# TF.net
KiCad netlist of a schematic drawn in Altium Designer
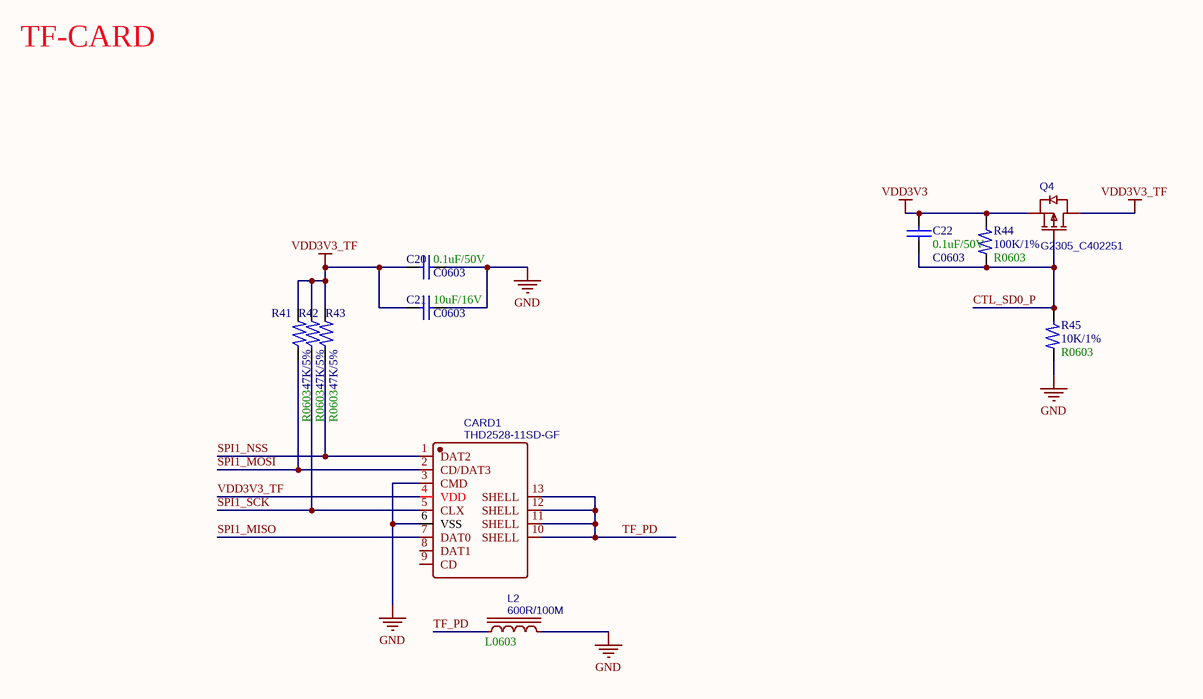
[diagram p0: TF.SchDoc]

(export (version "E")
  (design (tool "Eeschema 10.0.6"))
  (components
    (comp (ref "C20")
      (value "0.1uF/50V")
      (footprint "0603_C")
      (description "Capacitor")
      (fields (field (name "ALTIUM_VALUE") "C0603"))
      (libsource (lib "*") (part "CAP"))
    )
    (comp (ref "C21")
      (value "10uF/16V")
      (footprint "0603_C")
      (description "Capacitor")
      (fields (field (name "ALTIUM_VALUE") "C0603"))
      (libsource (lib "*") (part "CAP"))
    )
    (comp (ref "C22")
      (value "0.1uF/50V")
      (footprint "0603_C")
      (description "Capacitor")
      (fields (field (name "ALTIUM_VALUE") "C0603"))
      (libsource (lib "*") (part "CAP"))
    )
    (comp (ref "CARD1")
      (value "THD2528-11SD-GF")
      (footprint "TF-SMD_THD2528-11SD-GF")
      (fields (field (name "BOM_SUPPLIER PART") "C283232") (field (name "CONTRIBUTOR") "LCSC"))
      (libsource (lib "altium-import") (part "root_0_THD2528-11SD-GF_"))
    )
    (comp (ref "L2")
      (value "600R/100M")
      (footprint "0603_L")
      (fields
        (field (name "BOM_SUPPLIER PART") "C494701")
        (field (name "BOM_MANUFACTURER PART") "SCBM160808U600T")
        (field (name "ALTIUM_UNNAMED_1") "L0603")
        (field (name "CONTRIBUTOR") "LCSC")
      )
      (libsource (lib "altium-import") (part "root_0_SCBM160808U600T_"))
    )
    (comp (ref "Q4")
      (value "G2305_C402251")
      (footprint "SOT-23-3L")
      (fields
        (field (name "BOM_SUPPLIER PART") "C402251")
        (field (name "BOM_MANUFACTURER PART") "G2305")
        (field (name "CONTRIBUTOR") "LCSC")
      )
      (libsource (lib "altium-import") (part "root_1_mirrored_G2305_C402251_"))
    )
    (comp (ref "R41") (value "47K/5%") (footprint "R0603") (libsource (lib "*") (part "电阻")))
    (comp (ref "R42") (value "47K/5%") (footprint "R0603") (libsource (lib "*") (part "电阻")))
    (comp (ref "R43") (value "47K/5%") (footprint "R0603") (libsource (lib "*") (part "电阻")))
    (comp (ref "R44") (value "100K/1%") (footprint "R0603") (libsource (lib "*") (part "电阻")))
    (comp (ref "R45") (value "10K/1%") (footprint "R0603") (libsource (lib "*") (part "电阻")))
  )
  (nets
    (net (code "1") (name "/CTL_SD0_P") (class "Default")
      (node (ref "C22") (pin "2") (pinfunction "2_2") (pintype "passive"))
      (node (ref "Q4") (pin "1") (pinfunction "G_1") (pintype "passive"))
      (node (ref "R44") (pin "1") (pintype "passive"))
      (node (ref "R45") (pin "2") (pintype "passive"))
    )
    (net (code "2") (name "/SPI1_MISO") (class "Default")
      (node (ref "CARD1") (pin "7") (pinfunction "DAT0_7") (pintype "passive"))
    )
    (net (code "3") (name "/SPI1_MOSI") (class "Default")
      (node (ref "CARD1") (pin "2") (pinfunction "CD/DAT3_2") (pintype "passive"))
      (node (ref "R41") (pin "2") (pintype "passive"))
    )
    (net (code "4") (name "/SPI1_NSS") (class "Default")
      (node (ref "CARD1") (pin "1") (pinfunction "DAT2_1") (pintype "passive"))
      (node (ref "R43") (pin "2") (pintype "passive"))
    )
    (net (code "5") (name "/SPI1_SCK") (class "Default")
      (node (ref "CARD1") (pin "5") (pinfunction "CLX_5") (pintype "passive"))
      (node (ref "R42") (pin "2") (pintype "passive"))
    )
    (net (code "6") (name "/TF_PD") (class "Default")
      (node (ref "CARD1") (pin "10") (pinfunction "SHELL_10") (pintype "passive"))
      (node (ref "CARD1") (pin "11") (pinfunction "SHELL_11") (pintype "passive"))
      (node (ref "CARD1") (pin "12") (pinfunction "SHELL_12") (pintype "passive"))
      (node (ref "CARD1") (pin "13") (pinfunction "SHELL_13") (pintype "passive"))
      (node (ref "L2") (pin "1") (pinfunction "1_1") (pintype "passive"))
    )
    (net (code "7") (name "GND") (class "Default")
      (node (ref "C20") (pin "2") (pinfunction "2_2") (pintype "passive"))
      (node (ref "C21") (pin "2") (pinfunction "2_2") (pintype "passive"))
      (node (ref "CARD1") (pin "3") (pinfunction "CMD_3") (pintype "passive"))
      (node (ref "CARD1") (pin "6") (pinfunction "VSS_6") (pintype "passive"))
      (node (ref "L2") (pin "2") (pinfunction "2_2") (pintype "passive"))
      (node (ref "R45") (pin "1") (pintype "passive"))
    )
    (net (code "8") (name "VDD3V3") (class "Default")
      (node (ref "C22") (pin "1") (pinfunction "1_1") (pintype "passive"))
      (node (ref "Q4") (pin "2") (pinfunction "S_2") (pintype "passive"))
      (node (ref "R44") (pin "2") (pintype "passive"))
    )
    (net (code "9") (name "VDD3V3_TF") (class "Default")
      (node (ref "C20") (pin "1") (pinfunction "1_1") (pintype "passive"))
      (node (ref "C21") (pin "1") (pinfunction "1_1") (pintype "passive"))
      (node (ref "CARD1") (pin "4") (pinfunction "VDD_4") (pintype "passive"))
      (node (ref "Q4") (pin "3") (pinfunction "D_3") (pintype "passive"))
      (node (ref "R41") (pin "1") (pintype "passive"))
      (node (ref "R42") (pin "1") (pintype "passive"))
      (node (ref "R43") (pin "1") (pintype "passive"))
    )
    (net (code "10") (name "unconnected-(CARD1-CD-Pad9)") (class "Default")
      (node (ref "CARD1") (pin "9") (pinfunction "CD_9") (pintype "passive"))
    )
    (net (code "11") (name "unconnected-(CARD1-DAT1-Pad8)") (class "Default")
      (node (ref "CARD1") (pin "8") (pinfunction "DAT1_8") (pintype "passive"))
    )
  )
)
